# AD9833_DDS.net
KiCad netlist of a schematic drawn in EasyEDA Pro
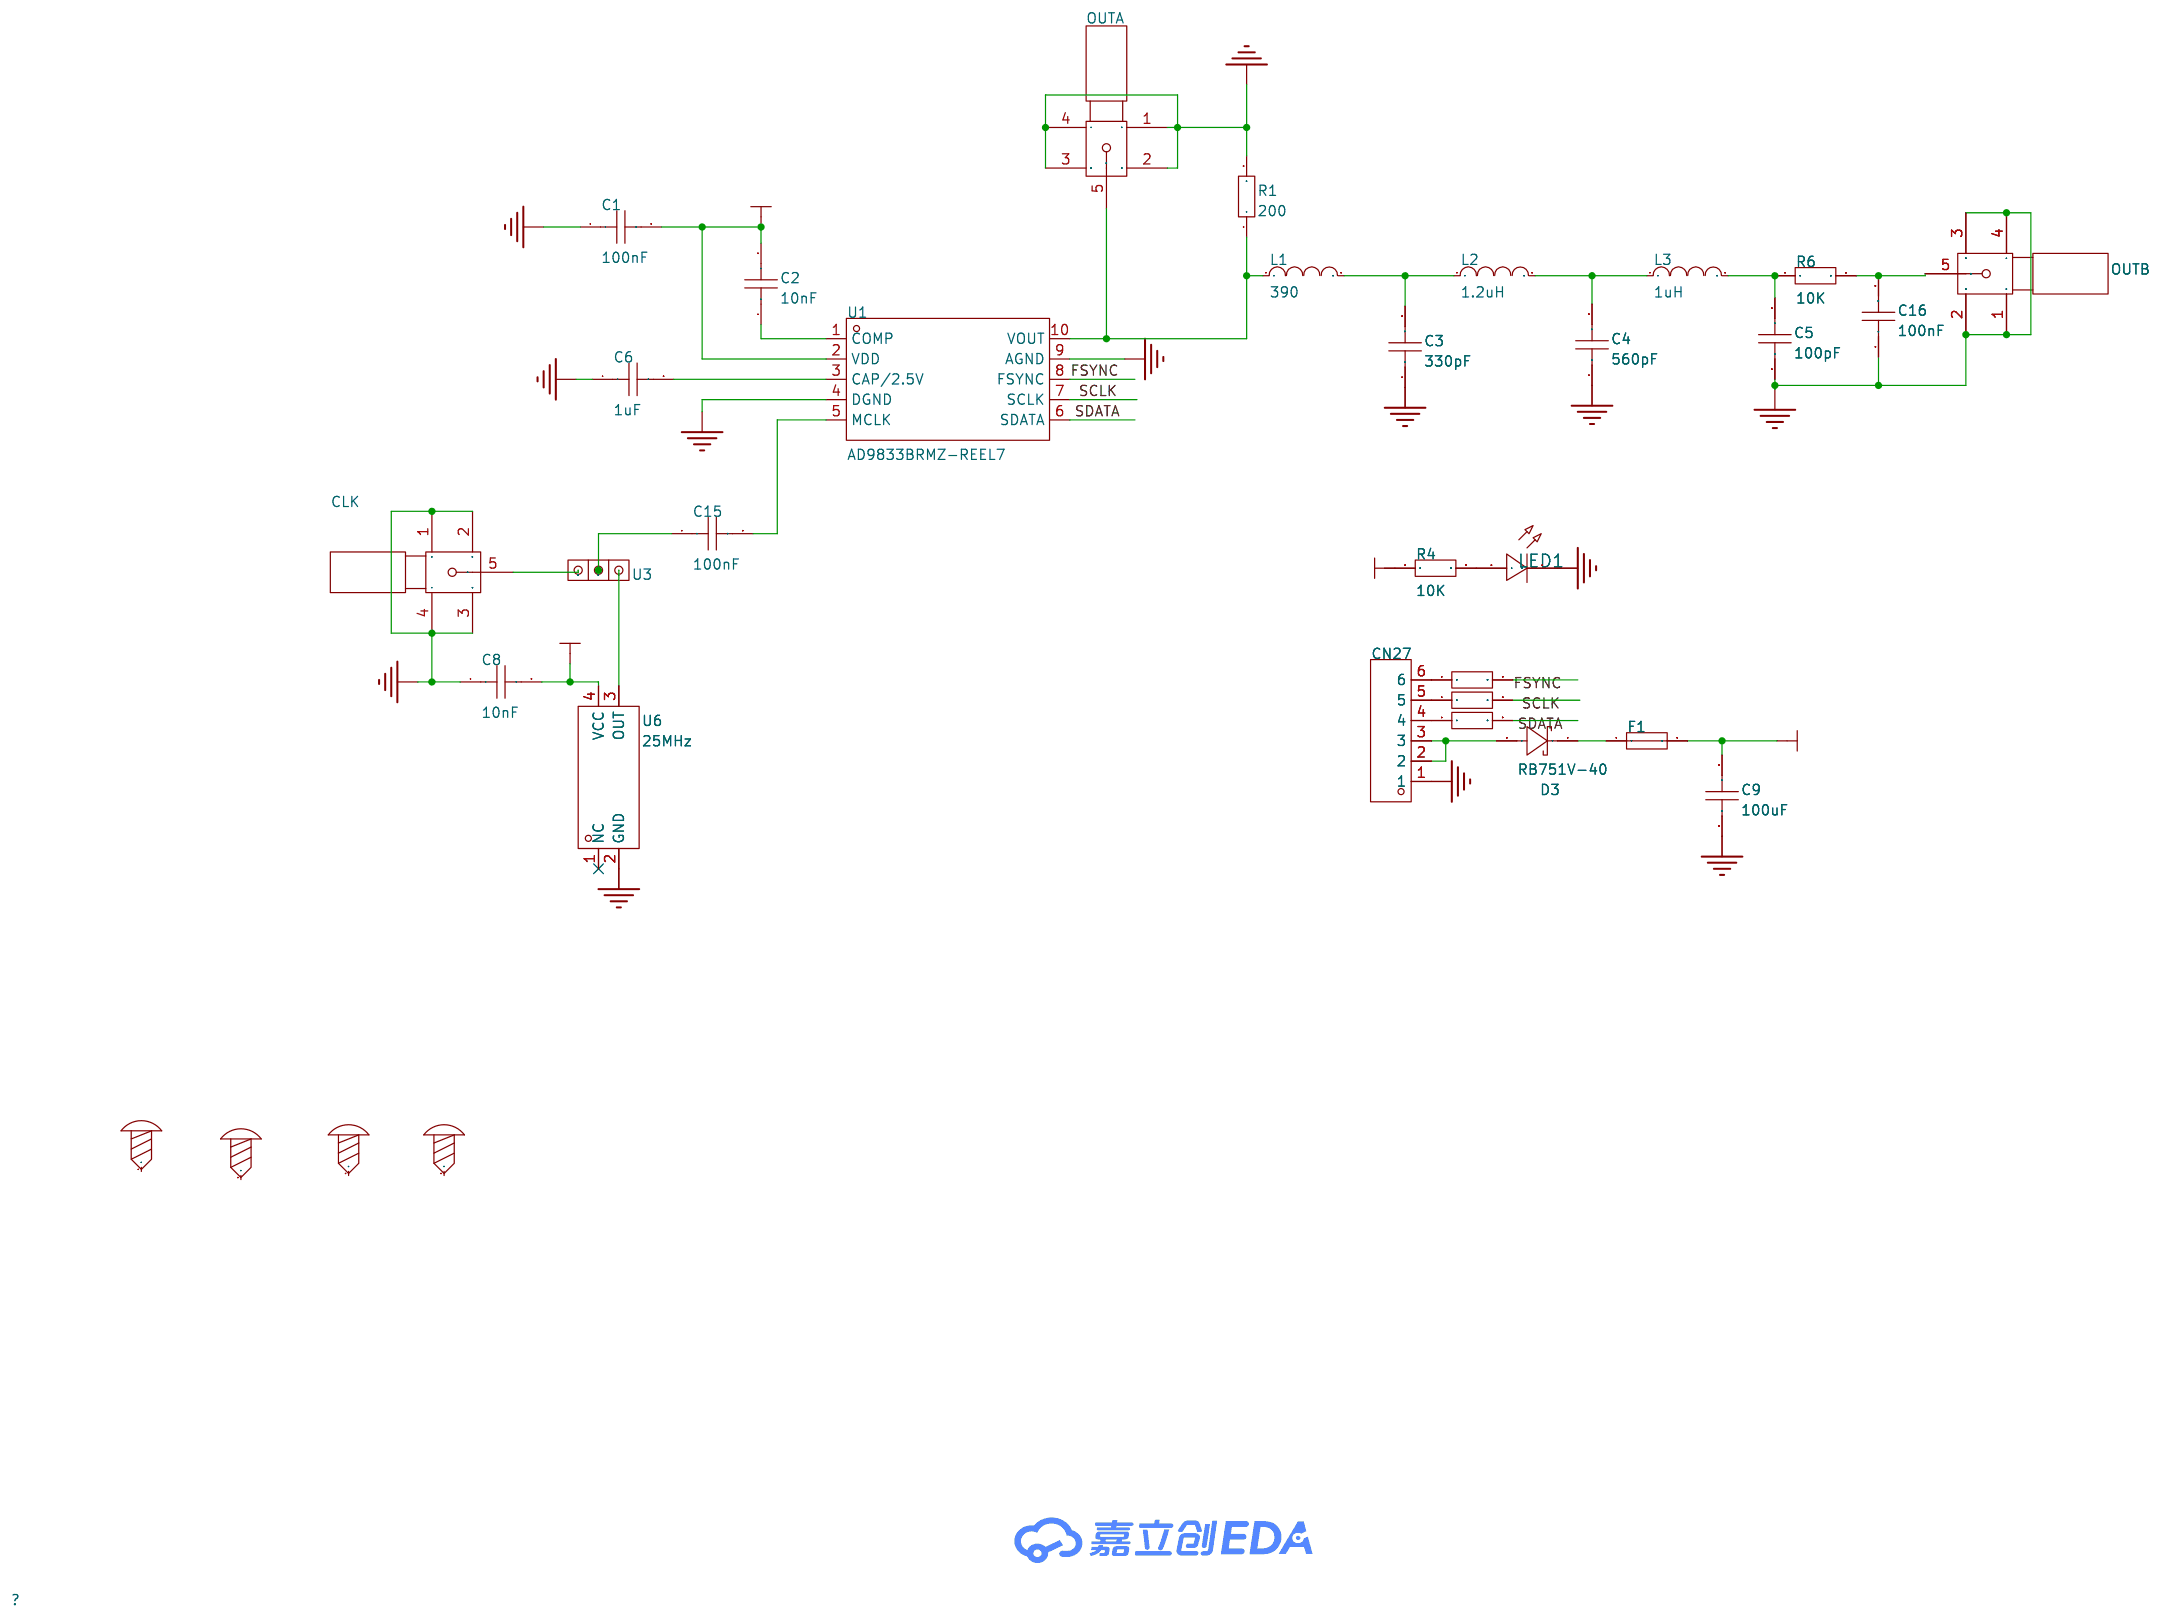
[diagram p0: schematic sheet]

(export (version "E")
  (design (tool "Eeschema 10.0.6"))
  (components
    (comp (ref "C1")
      (value "100nF")
      (footprint "easyedapro:C0805")
      (libsource (lib "easyedapro") (part "CapAcitance"))
    )
    (comp (ref "C2")
      (value "10nF")
      (footprint "easyedapro:C0805")
      (libsource (lib "easyedapro") (part "CapAcitance"))
    )
    (comp (ref "C3")
      (value "330pF")
      (footprint "easyedapro:C0805")
      (libsource (lib "easyedapro") (part "CapAcitance"))
    )
    (comp (ref "C4")
      (value "560pF")
      (footprint "easyedapro:C0805")
      (libsource (lib "easyedapro") (part "CapAcitance"))
    )
    (comp (ref "C5")
      (value "100pF")
      (footprint "easyedapro:C0805")
      (libsource (lib "easyedapro") (part "CapAcitance"))
    )
    (comp (ref "C6")
      (value "1uF")
      (footprint "easyedapro:C0805")
      (libsource (lib "easyedapro") (part "CapAcitance"))
    )
    (comp (ref "C8")
      (value "10nF")
      (footprint "easyedapro:C0805")
      (libsource (lib "easyedapro") (part "CapAcitance"))
    )
    (comp (ref "C9")
      (value "100uF")
      (footprint "easyedapro:C1210")
      (description "容值:100uF;精度:±20%;额定电压:6.3V;材质(温度系数):X5R;")
      (fields
        (field (name "Manufacturer Part") "GRM32ER60J107ME20L")
        (field (name "Manufacturer") "muRata(村田)")
      )
      (libsource (lib "easyedapro") (part "GRM32ER60J107ME20L"))
    )
    (comp (ref "C15")
      (value "100nF")
      (footprint "easyedapro:C0805")
      (libsource (lib "easyedapro") (part "CapAcitance"))
    )
    (comp (ref "C16")
      (value "100nF")
      (footprint "easyedapro:C0805")
      (libsource (lib "easyedapro") (part "CapAcitance"))
    )
    (comp (ref "CLK") (value "~") (footprint "easyedapro:SMA") (libsource (lib "easyedapro") (part "SMA")))
    (comp (ref "CN27")
      (value "XH2.54*6P_直插")
      (footprint "easyedapro:CONN-TH_XH2.54-6P")
      (libsource (lib "easyedapro") (part "XH2.54*6P_直插"))
    )
    (comp (ref "D3")
      (value "RB751V-40")
      (footprint "easyedapro:SOD-323_L1.7-W1.3-LS2.6-RD-1")
      (description "二极管配置:独立式;正向压降(Vf):370mV@1mA;直流反向耐压(Vr):40V;平均整流电流(Io):30mA;")
      (fields (field (name "Manufacturer") "宏迦橙"))
      (libsource (lib "easyedapro") (part "RB751V-40_C7502691"))
    )
    (comp (ref "F1")
      (value "BSMD0805-003-30V")
      (footprint "easyedapro:F0805")
      (description "耐压:30V;最大电流:20A;保持电流(Ih):30mA;跳闸电流:90mA;")
      (fields (field (name "Manufacturer") "BHFUSE(佰宏)"))
      (libsource (lib "easyedapro") (part "BSMD0805-003-30V"))
    )
    (comp (ref "L1")
      (value "390")
      (footprint "easyedapro:L0805")
      (libsource (lib "easyedapro") (part "SDFL2012S100KTF"))
    )
    (comp (ref "L2")
      (value "1.2uH")
      (footprint "easyedapro:L0805")
      (libsource (lib "easyedapro") (part "SDFL2012S100KTF"))
    )
    (comp (ref "L3")
      (value "1uH")
      (footprint "easyedapro:L0805")
      (libsource (lib "easyedapro") (part "SDFL2012S100KTF"))
    )
    (comp (ref "LED1")
      (value "~")
      (footprint "easyedapro:LED_0805")
      (libsource (lib "easyedapro") (part "LED_R"))
    )
    (comp (ref "OUTA") (value "~") (footprint "easyedapro:SMA") (libsource (lib "easyedapro") (part "SMA")))
    (comp (ref "OUTB") (value "~") (footprint "easyedapro:SMA") (libsource (lib "easyedapro") (part "SMA")))
    (comp (ref "R1") (value "200") (footprint "easyedapro:R0805") (libsource (lib "easyedapro") (part "电阻")))
    (comp (ref "R2") (value "10K") (footprint "easyedapro:R0805") (libsource (lib "easyedapro") (part "电阻")))
    (comp (ref "R3") (value "10K") (footprint "easyedapro:R0805") (libsource (lib "easyedapro") (part "电阻")))
    (comp (ref "R4") (value "10K") (footprint "easyedapro:R0805") (libsource (lib "easyedapro") (part "电阻")))
    (comp (ref "R5") (value "10K") (footprint "easyedapro:R0805") (libsource (lib "easyedapro") (part "电阻")))
    (comp (ref "R6") (value "10K") (footprint "easyedapro:R0805") (libsource (lib "easyedapro") (part "电阻")))
    (comp (ref "SCREW1")
      (value "~")
      (footprint "easyedapro:M2螺丝")
      (libsource (lib "easyedapro") (part "螺丝孔"))
    )
    (comp (ref "SCREW2")
      (value "~")
      (footprint "easyedapro:M2螺丝")
      (libsource (lib "easyedapro") (part "螺丝孔"))
    )
    (comp (ref "SCREW3")
      (value "~")
      (footprint "easyedapro:M2螺丝")
      (libsource (lib "easyedapro") (part "螺丝孔"))
    )
    (comp (ref "SCREW4")
      (value "~")
      (footprint "easyedapro:M2螺丝")
      (libsource (lib "easyedapro") (part "螺丝孔"))
    )
    (comp (ref "U1")
      (value "AD9833BRMZ-REEL7")
      (footprint "easyedapro:MSOP-10_L3.0-W3.0-P0.50-LS5.0-BL")
      (description "电源电压:2.3V~5.5V;分辨率(位):10;自宽调谐(最大值):28b;")
      (fields (field (name "Manufacturer") "ADI(亚德诺)"))
      (libsource (lib "easyedapro") (part "AD9833BRMZ"))
    )
    (comp (ref "U3") (value "~") (footprint "easyedapro:1*3跳线") (libsource (lib "easyedapro") (part "1*3跳线")))
    (comp (ref "U6")
      (value "25MHz")
      (footprint "easyedapro:OSC-SMD_4P-L7.0-W5.0-BL")
      (description "频率:25MHz;输出模式:HCMOS;工作电压:3.3V;频率稳定度(全温):±50ppm;")
      (fields
        (field (name "Manufacturer Part") "CO75H4-25.000-33GDTST")
        (field (name "Manufacturer") "HCI(杭晶)")
      )
      (libsource (lib "easyedapro") (part "CO75H4-25.000-33GDTST"))
    )
  )
  (nets
    (net (code "1") (name "/FSYNC") (class "Default")
      (node (ref "R3") (pin "2") (pinfunction "2_2") (pintype "input"))
      (node (ref "U1") (pin "8") (pinfunction "FSYNC_8") (pintype "unspecified"))
    )
    (net (code "2") (name "/SCLK") (class "Default")
      (node (ref "R2") (pin "2") (pinfunction "2_2") (pintype "input"))
      (node (ref "U1") (pin "7") (pinfunction "SCLK_7") (pintype "unspecified"))
    )
    (net (code "3") (name "/SDATA") (class "Default")
      (node (ref "R5") (pin "2") (pinfunction "2_2") (pintype "input"))
      (node (ref "U1") (pin "6") (pinfunction "SDATA_6") (pintype "unspecified"))
    )
    (net (code "4") (name "DVDD") (class "Default")
      (node (ref "C1") (pin "2") (pinfunction "2_2") (pintype "input"))
      (node (ref "C2") (pin "2") (pinfunction "2_2") (pintype "input"))
      (node (ref "C8") (pin "2") (pinfunction "2_2") (pintype "input"))
      (node (ref "C9") (pin "2") (pinfunction "2_2") (pintype "unspecified"))
      (node (ref "F1") (pin "2") (pinfunction "2_2") (pintype "unspecified"))
      (node (ref "R4") (pin "1") (pinfunction "1_1") (pintype "input"))
      (node (ref "U1") (pin "2") (pinfunction "VDD_2") (pintype "unspecified"))
      (node (ref "U6") (pin "4") (pinfunction "VCC_4") (pintype "unspecified"))
    )
    (net (code "5") (name "GND") (class "Default")
      (node (ref "C1") (pin "1") (pinfunction "1_1") (pintype "input"))
      (node (ref "C16") (pin "1") (pinfunction "1_1") (pintype "input"))
      (node (ref "C3") (pin "1") (pinfunction "1_1") (pintype "input"))
      (node (ref "C4") (pin "1") (pinfunction "1_1") (pintype "input"))
      (node (ref "C5") (pin "1") (pinfunction "1_1") (pintype "input"))
      (node (ref "C6") (pin "1") (pinfunction "1_1") (pintype "input"))
      (node (ref "C8") (pin "1") (pinfunction "1_1") (pintype "input"))
      (node (ref "C9") (pin "1") (pinfunction "1_1") (pintype "unspecified"))
      (node (ref "CLK") (pin "1") (pinfunction "1_1") (pintype "input"))
      (node (ref "CLK") (pin "2") (pinfunction "2_2") (pintype "input"))
      (node (ref "CLK") (pin "3") (pinfunction "3_3") (pintype "input"))
      (node (ref "CLK") (pin "4") (pinfunction "4_4") (pintype "input"))
      (node (ref "CN27") (pin "1") (pinfunction "1_1") (pintype "unspecified"))
      (node (ref "LED1") (pin "1") (pinfunction "C_1") (pintype "input"))
      (node (ref "OUTA") (pin "1") (pinfunction "1_1") (pintype "input"))
      (node (ref "OUTA") (pin "2") (pinfunction "2_2") (pintype "input"))
      (node (ref "OUTA") (pin "3") (pinfunction "3_3") (pintype "input"))
      (node (ref "OUTA") (pin "4") (pinfunction "4_4") (pintype "input"))
      (node (ref "OUTB") (pin "1") (pinfunction "1_1") (pintype "input"))
      (node (ref "OUTB") (pin "2") (pinfunction "2_2") (pintype "input"))
      (node (ref "OUTB") (pin "3") (pinfunction "3_3") (pintype "input"))
      (node (ref "OUTB") (pin "4") (pinfunction "4_4") (pintype "input"))
      (node (ref "R1") (pin "2") (pinfunction "2_2") (pintype "input"))
      (node (ref "U1") (pin "4") (pinfunction "DGND_4") (pintype "unspecified"))
      (node (ref "U1") (pin "9") (pinfunction "AGND_9") (pintype "unspecified"))
      (node (ref "U6") (pin "2") (pinfunction "GND_2") (pintype "unspecified"))
    )
    (net (code "6") (name "Net-(C3-Pad2)") (class "Default")
      (node (ref "C3") (pin "2") (pinfunction "2_2") (pintype "input"))
      (node (ref "L1") (pin "2") (pinfunction "2_2") (pintype "unspecified"))
      (node (ref "L2") (pin "1") (pinfunction "1_1") (pintype "unspecified"))
    )
    (net (code "7") (name "Net-(C4-Pad2)") (class "Default")
      (node (ref "C4") (pin "2") (pinfunction "2_2") (pintype "input"))
      (node (ref "L2") (pin "2") (pinfunction "2_2") (pintype "unspecified"))
      (node (ref "L3") (pin "1") (pinfunction "1_1") (pintype "unspecified"))
    )
    (net (code "8") (name "Net-(C5-Pad2)") (class "Default")
      (node (ref "C5") (pin "2") (pinfunction "2_2") (pintype "input"))
      (node (ref "L3") (pin "2") (pinfunction "2_2") (pintype "unspecified"))
      (node (ref "R6") (pin "1") (pinfunction "1_1") (pintype "input"))
    )
    (net (code "9") (name "Net-(C15-Pad1)") (class "Default")
      (node (ref "C15") (pin "1") (pinfunction "1_1") (pintype "input"))
      (node (ref "U3") (pin "2") (pinfunction "2_2") (pintype "input"))
    )
    (net (code "10") (name "Net-(C16-Pad2)") (class "Default")
      (node (ref "C16") (pin "2") (pinfunction "2_2") (pintype "input"))
      (node (ref "OUTB") (pin "5") (pinfunction "5_5") (pintype "input"))
      (node (ref "R6") (pin "2") (pinfunction "2_2") (pintype "input"))
    )
    (net (code "11") (name "Net-(CLK-Pad5)") (class "Default")
      (node (ref "CLK") (pin "5") (pinfunction "5_5") (pintype "input"))
      (node (ref "U3") (pin "3") (pinfunction "3_3") (pintype "input"))
    )
    (net (code "12") (name "Net-(CN27-Pad4)") (class "Default")
      (node (ref "CN27") (pin "4") (pinfunction "4_4") (pintype "unspecified"))
      (node (ref "R5") (pin "1") (pinfunction "1_1") (pintype "input"))
    )
    (net (code "13") (name "Net-(CN27-Pad5)") (class "Default")
      (node (ref "CN27") (pin "5") (pinfunction "5_5") (pintype "unspecified"))
      (node (ref "R2") (pin "1") (pinfunction "1_1") (pintype "input"))
    )
    (net (code "14") (name "Net-(CN27-Pad6)") (class "Default")
      (node (ref "CN27") (pin "6") (pinfunction "6_6") (pintype "unspecified"))
      (node (ref "R3") (pin "1") (pinfunction "1_1") (pintype "input"))
    )
    (net (code "15") (name "Net-(D3-A)") (class "Default")
      (node (ref "CN27") (pin "2") (pinfunction "2_2") (pintype "unspecified"))
      (node (ref "CN27") (pin "3") (pinfunction "3_3") (pintype "unspecified"))
      (node (ref "D3") (pin "2") (pinfunction "A_2") (pintype "unspecified"))
    )
    (net (code "16") (name "Net-(D3-K)") (class "Default")
      (node (ref "D3") (pin "1") (pinfunction "K_1") (pintype "unspecified"))
      (node (ref "F1") (pin "1") (pinfunction "1_1") (pintype "unspecified"))
    )
    (net (code "17") (name "Net-(LED1-A)") (class "Default")
      (node (ref "LED1") (pin "2") (pinfunction "A_2") (pintype "input"))
      (node (ref "R4") (pin "2") (pinfunction "2_2") (pintype "input"))
    )
    (net (code "18") (name "Net-(U1-CAP{slash}2.5V)") (class "Default")
      (node (ref "C6") (pin "2") (pinfunction "2_2") (pintype "input"))
      (node (ref "U1") (pin "3") (pinfunction "CAP/2.5V_3") (pintype "unspecified"))
    )
    (net (code "19") (name "Net-(U1-COMP)") (class "Default")
      (node (ref "C2") (pin "1") (pinfunction "1_1") (pintype "input"))
      (node (ref "U1") (pin "1") (pinfunction "COMP_1") (pintype "unspecified"))
    )
    (net (code "20") (name "Net-(U1-MCLK)") (class "Default")
      (node (ref "C15") (pin "2") (pinfunction "2_2") (pintype "input"))
      (node (ref "U1") (pin "5") (pinfunction "MCLK_5") (pintype "unspecified"))
    )
    (net (code "21") (name "Net-(U1-VOUT)") (class "Default")
      (node (ref "L1") (pin "1") (pinfunction "1_1") (pintype "unspecified"))
      (node (ref "OUTA") (pin "5") (pinfunction "5_5") (pintype "input"))
      (node (ref "R1") (pin "1") (pinfunction "1_1") (pintype "input"))
      (node (ref "U1") (pin "10") (pinfunction "VOUT_10") (pintype "unspecified"))
    )
    (net (code "22") (name "Net-(U6-OUT)") (class "Default")
      (node (ref "U3") (pin "1") (pinfunction "1_1") (pintype "input"))
      (node (ref "U6") (pin "3") (pinfunction "OUT_3") (pintype "unspecified"))
    )
    (net (code "23") (name "unconnected-(SCREW1-Pad1)") (class "Default")
      (node (ref "SCREW1") (pin "1") (pinfunction "1_1") (pintype "input"))
    )
    (net (code "24") (name "unconnected-(SCREW2-Pad1)") (class "Default")
      (node (ref "SCREW2") (pin "1") (pinfunction "1_1") (pintype "input"))
    )
    (net (code "25") (name "unconnected-(SCREW3-Pad1)") (class "Default")
      (node (ref "SCREW3") (pin "1") (pinfunction "1_1") (pintype "input"))
    )
    (net (code "26") (name "unconnected-(SCREW4-Pad1)") (class "Default")
      (node (ref "SCREW4") (pin "1") (pinfunction "1_1") (pintype "input"))
    )
    (net (code "27") (name "unconnected-(U6-NC-Pad1)") (class "Default")
      (node (ref "U6") (pin "1") (pinfunction "NC_1") (pintype "unspecified+no_connect"))
    )
  )
)
